# 1-Schematic_TRD_Line_follower_robot.net
KiCad netlist of a schematic drawn in EasyEDA
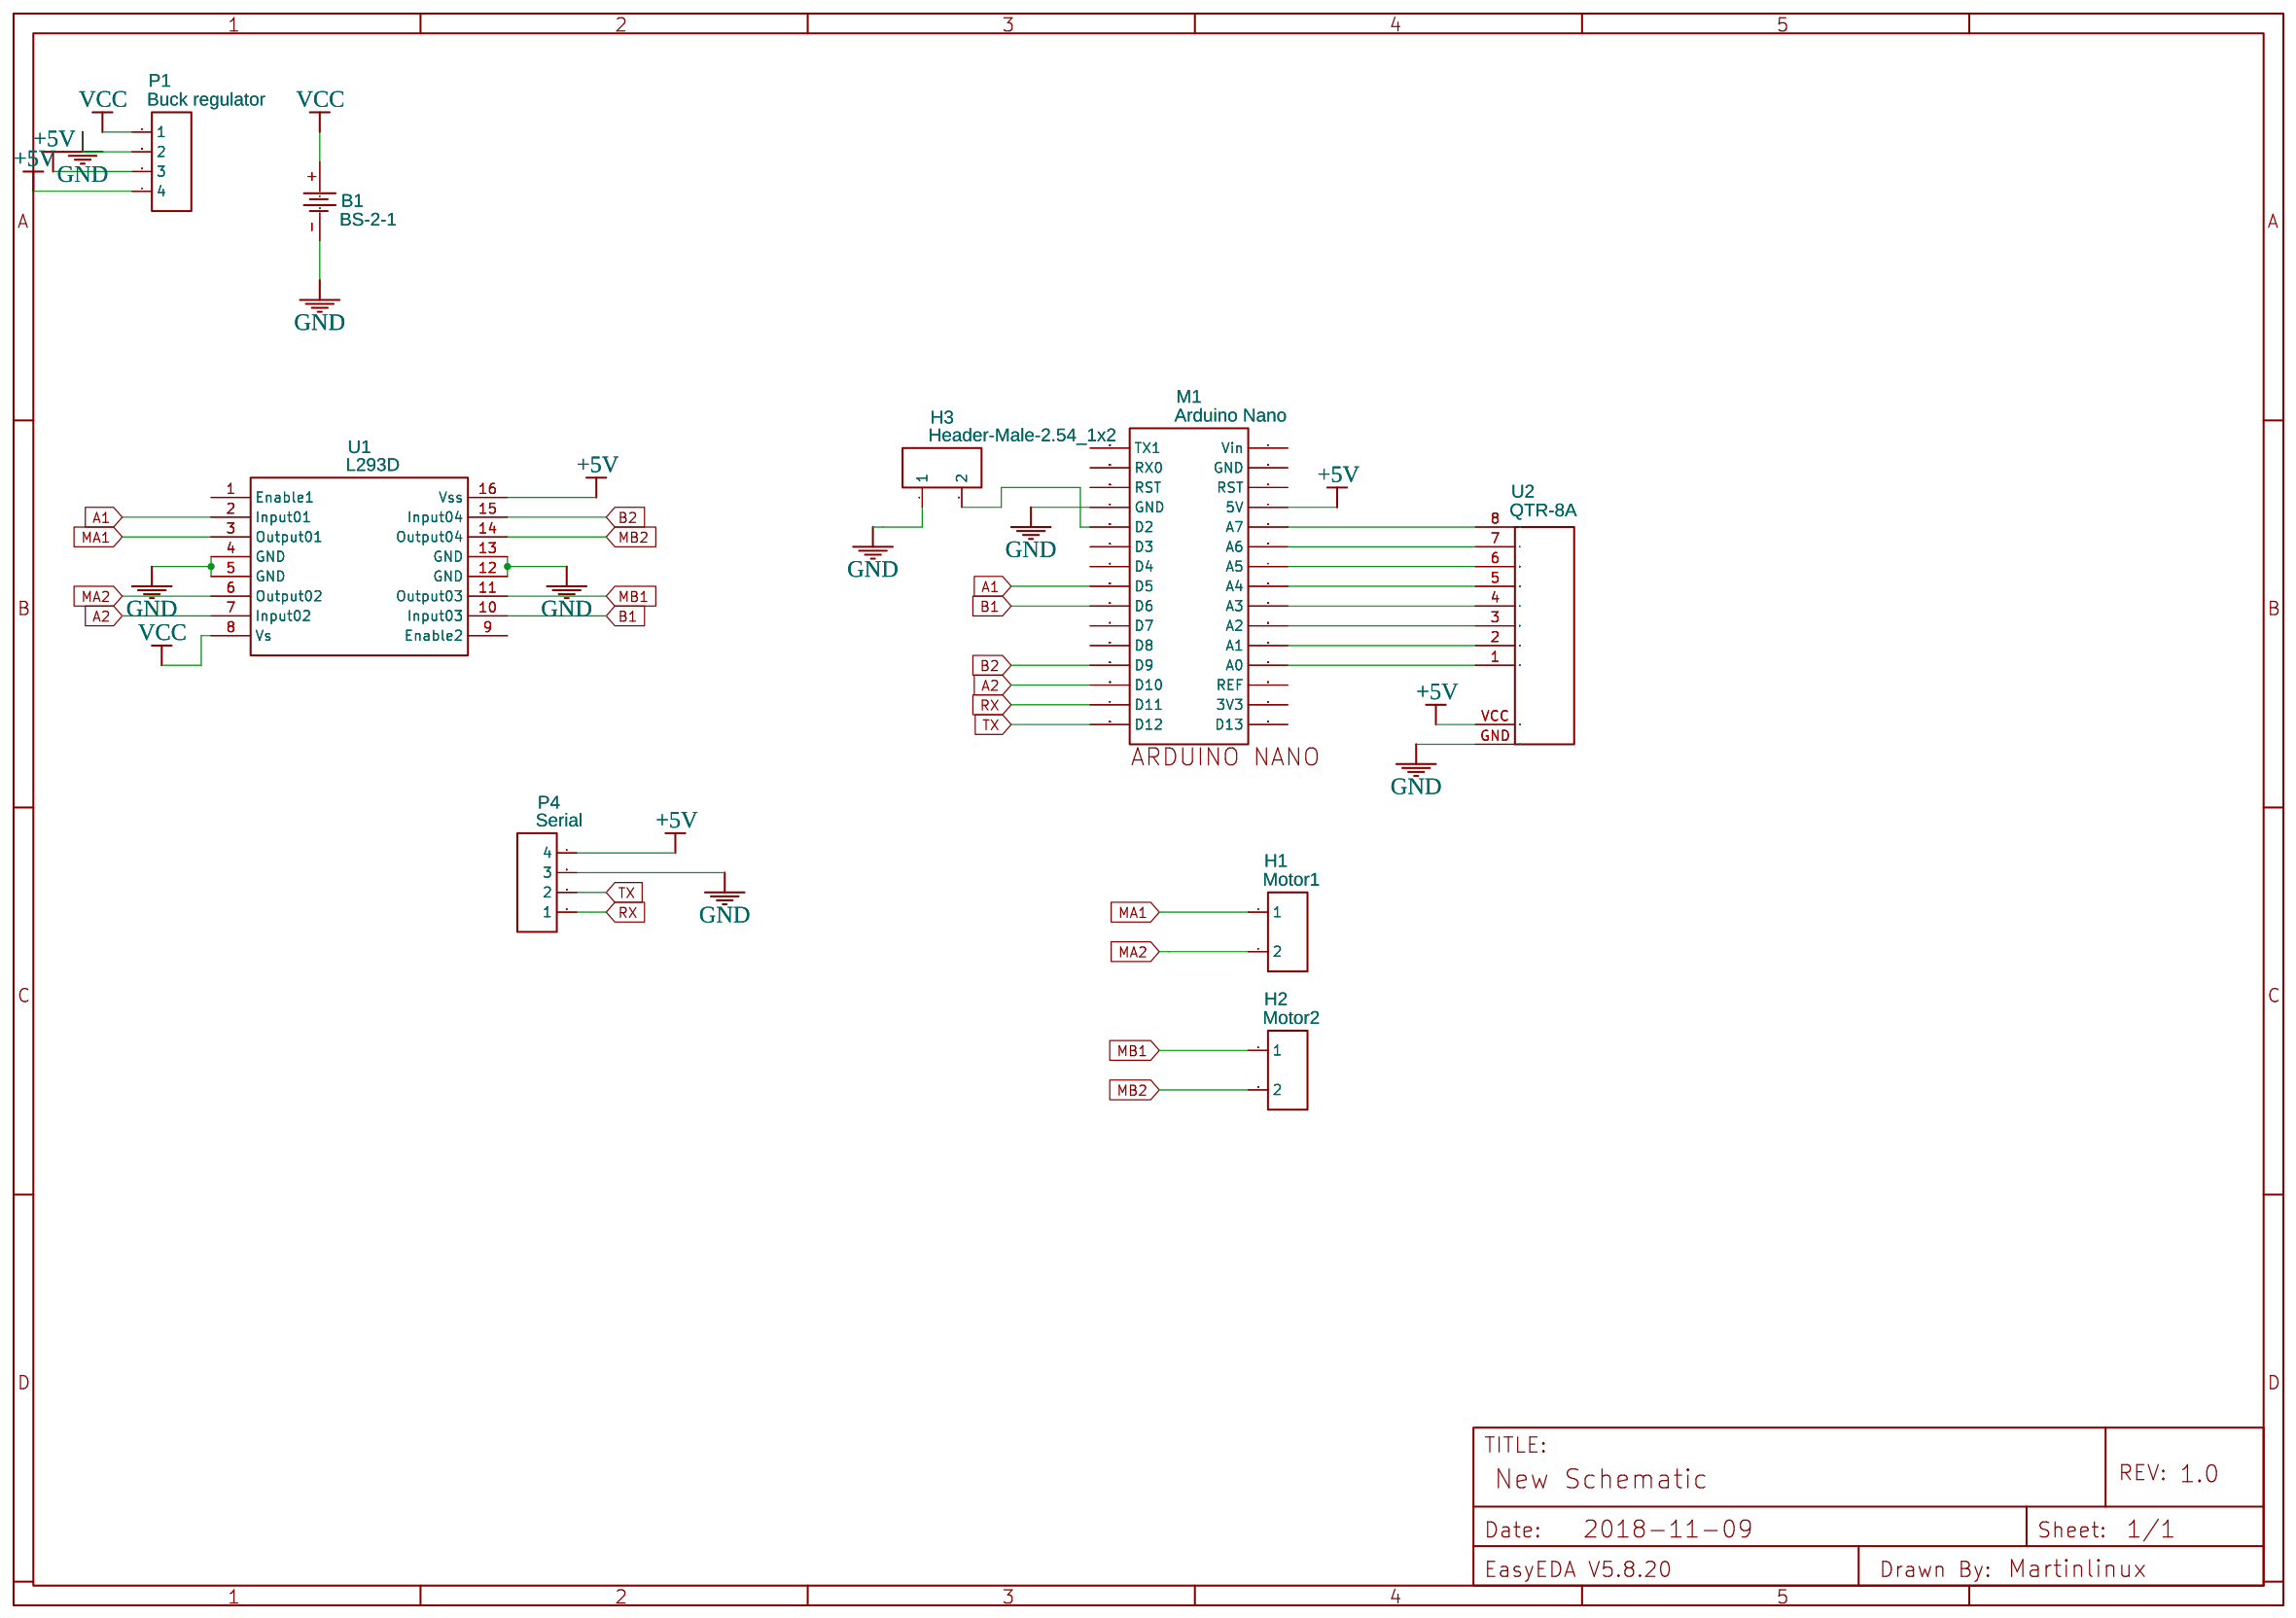
[diagram p0: schematic sheet]

(export (version "E")
  (design (tool "Eeschema 10.0.6"))
  (components
    (comp (ref "B1")
      (value "BS-2-1")
      (fields (field (name "BOM_Supplier Part") "C70376"))
      (libsource (lib "") (part "Unknown_155_95"))
    )
    (comp (ref "H1")
      (value "Motor1")
      (fields (field (name "BOM_Manufacturer Part") "826629-2") (field (name "BOM_Supplier Part") "C86471"))
      (libsource (lib "") (part "Unknown_640_465"))
    )
    (comp (ref "H2")
      (value "Motor2")
      (fields (field (name "BOM_Manufacturer Part") "826629-2") (field (name "BOM_Supplier Part") "C86471"))
      (libsource (lib "") (part "Unknown_640_535"))
    )
    (comp (ref "H3")
      (value "Header-Male-2.54_1x2")
      (fields (field (name "BOM_Manufacturer Part") "826629-2") (field (name "BOM_Supplier Part") "C86471"))
      (libsource (lib "") (part "Unknown_470_235"))
    )
    (comp (ref "M1") (value "Arduino Nano") (libsource (lib "") (part "Unknown_565_210")))
    (comp (ref "P1")
      (value "Buck regulator")
      (fields
        (field (name "BOM_Manufacturer Part") "Header-Female-2.54_1x4")
        (field (name "BOM_Supplier Part") "C124413")
      )
      (libsource (lib "") (part "Unknown_75_75"))
    )
    (comp (ref "P4")
      (value "Serial")
      (fields
        (field (name "BOM_Manufacturer Part") "Header-Female-2.54_1x4")
        (field (name "BOM_Supplier Part") "C124413")
      )
      (libsource (lib "") (part "Unknown_270_440"))
    )
    (comp (ref "U1")
      (value "L293D")
      (fields (field (name "BOM_Supplier Part") "C12340"))
      (libsource (lib "") (part "Unknown_175_280"))
    )
    (comp (ref "U2")
      (value "QTR-8A")
      (fields (field (name "BOM_Manufacturer Part") "?"))
      (libsource (lib "") (part "Unknown_800_360"))
    )
  )
  (nets
    (net (code "1") (name "+5V") (class "Default")
      (node (ref "M1") (pin "4") (pinfunction "5V_4") (pintype "unspecified"))
      (node (ref "P1") (pin "3") (pinfunction "3_3") (pintype "input"))
      (node (ref "P1") (pin "4") (pinfunction "4_4") (pintype "input"))
      (node (ref "P4") (pin "4") (pinfunction "4_4") (pintype "input"))
      (node (ref "U1") (pin "16") (pinfunction "Vss_16") (pintype "unspecified"))
      (node (ref "U2") (pin "VCC") (pinfunction "9_VCC") (pintype "unspecified"))
    )
    (net (code "2") (name "A1") (class "Default")
      (node (ref "M1") (pin "23") (pinfunction "D5_23") (pintype "unspecified"))
      (node (ref "U1") (pin "2") (pinfunction "Input01_2") (pintype "unspecified"))
    )
    (net (code "3") (name "A2") (class "Default")
      (node (ref "M1") (pin "18") (pinfunction "D10_18") (pintype "unspecified"))
      (node (ref "U1") (pin "7") (pinfunction "Input02_7") (pintype "unspecified"))
    )
    (net (code "4") (name "B1") (class "Default")
      (node (ref "M1") (pin "22") (pinfunction "D6_22") (pintype "unspecified"))
      (node (ref "U1") (pin "10") (pinfunction "Input03_10") (pintype "unspecified"))
    )
    (net (code "5") (name "B2") (class "Default")
      (node (ref "M1") (pin "19") (pinfunction "D9_19") (pintype "unspecified"))
      (node (ref "U1") (pin "15") (pinfunction "Input04_15") (pintype "unspecified"))
    )
    (net (code "6") (name "GND") (class "Default")
      (node (ref "B1") (pin "-") (pinfunction "2_-") (pintype "input"))
      (node (ref "H3") (pin "1") (pinfunction "1_1") (pintype "unspecified"))
      (node (ref "M1") (pin "27") (pinfunction "GND_27") (pintype "unspecified"))
      (node (ref "P1") (pin "2") (pinfunction "2_2") (pintype "input"))
      (node (ref "P4") (pin "3") (pinfunction "3_3") (pintype "input"))
      (node (ref "U1") (pin "12") (pinfunction "GND_12") (pintype "unspecified"))
      (node (ref "U1") (pin "13") (pinfunction "GND_13") (pintype "unspecified"))
      (node (ref "U1") (pin "4") (pinfunction "GND_4") (pintype "unspecified"))
      (node (ref "U1") (pin "5") (pinfunction "GND_5") (pintype "unspecified"))
      (node (ref "U2") (pin "GND") (pinfunction "1_GND") (pintype "unspecified"))
    )
    (net (code "7") (name "MA1") (class "Default")
      (node (ref "H1") (pin "1") (pinfunction "1_1") (pintype "unspecified"))
      (node (ref "U1") (pin "3") (pinfunction "Output01_3") (pintype "unspecified"))
    )
    (net (code "8") (name "MA2") (class "Default")
      (node (ref "H1") (pin "2") (pinfunction "2_2") (pintype "unspecified"))
      (node (ref "U1") (pin "6") (pinfunction "Output02_6") (pintype "unspecified"))
    )
    (net (code "9") (name "MB1") (class "Default")
      (node (ref "H2") (pin "1") (pinfunction "1_1") (pintype "unspecified"))
      (node (ref "U1") (pin "11") (pinfunction "Output03_11") (pintype "unspecified"))
    )
    (net (code "10") (name "MB2") (class "Default")
      (node (ref "H2") (pin "2") (pinfunction "2_2") (pintype "unspecified"))
      (node (ref "U1") (pin "14") (pinfunction "Output04_14") (pintype "unspecified"))
    )
    (net (code "11") (name "Net-(M1-A0)") (class "Default")
      (node (ref "M1") (pin "12") (pinfunction "A0_12") (pintype "unspecified"))
      (node (ref "U2") (pin "1") (pinfunction "1_1") (pintype "unspecified"))
    )
    (net (code "12") (name "Net-(M1-A1)") (class "Default")
      (node (ref "M1") (pin "11") (pinfunction "A1_11") (pintype "unspecified"))
      (node (ref "U2") (pin "2") (pinfunction "2_2") (pintype "unspecified"))
    )
    (net (code "13") (name "Net-(M1-A2)") (class "Default")
      (node (ref "M1") (pin "10") (pinfunction "A2_10") (pintype "unspecified"))
      (node (ref "U2") (pin "3") (pinfunction "3_3") (pintype "unspecified"))
    )
    (net (code "14") (name "Net-(M1-A3)") (class "Default")
      (node (ref "M1") (pin "9") (pinfunction "A3_9") (pintype "unspecified"))
      (node (ref "U2") (pin "4") (pinfunction "4_4") (pintype "unspecified"))
    )
    (net (code "15") (name "Net-(M1-A4)") (class "Default")
      (node (ref "M1") (pin "8") (pinfunction "A4_8") (pintype "unspecified"))
      (node (ref "U2") (pin "5") (pinfunction "5_5") (pintype "unspecified"))
    )
    (net (code "16") (name "Net-(M1-A5)") (class "Default")
      (node (ref "M1") (pin "7") (pinfunction "A5_7") (pintype "unspecified"))
      (node (ref "U2") (pin "6") (pinfunction "6_6") (pintype "unspecified"))
    )
    (net (code "17") (name "Net-(M1-A6)") (class "Default")
      (node (ref "M1") (pin "6") (pinfunction "A6_6") (pintype "unspecified"))
      (node (ref "U2") (pin "7") (pinfunction "7_7") (pintype "unspecified"))
    )
    (net (code "18") (name "Net-(M1-A7)") (class "Default")
      (node (ref "M1") (pin "5") (pinfunction "A7_5") (pintype "unspecified"))
      (node (ref "U2") (pin "8") (pinfunction "8_8") (pintype "unspecified"))
    )
    (net (code "19") (name "Net-(M1-D2)") (class "Default")
      (node (ref "H3") (pin "2") (pinfunction "2_2") (pintype "unspecified"))
      (node (ref "M1") (pin "26") (pinfunction "D2_26") (pintype "unspecified"))
    )
    (net (code "20") (name "RX") (class "Default")
      (node (ref "M1") (pin "17") (pinfunction "D11_17") (pintype "unspecified"))
      (node (ref "P4") (pin "1") (pinfunction "1_1") (pintype "input"))
    )
    (net (code "21") (name "TX") (class "Default")
      (node (ref "M1") (pin "16") (pinfunction "D12_16") (pintype "unspecified"))
      (node (ref "P4") (pin "2") (pinfunction "2_2") (pintype "input"))
    )
    (net (code "22") (name "VCC") (class "Default")
      (node (ref "B1") (pin "+") (pinfunction "1_+") (pintype "input"))
      (node (ref "P1") (pin "1") (pinfunction "1_1") (pintype "input"))
      (node (ref "U1") (pin "8") (pinfunction "Vs_8") (pintype "unspecified"))
    )
    (net (code "23") (name "unconnected-(M1-3V3-Pad14)") (class "Default")
      (node (ref "M1") (pin "14") (pinfunction "3V3_14") (pintype "unspecified"))
    )
    (net (code "24") (name "unconnected-(M1-D3-Pad25)") (class "Default")
      (node (ref "M1") (pin "25") (pinfunction "D3_25") (pintype "unspecified"))
    )
    (net (code "25") (name "unconnected-(M1-D4-Pad24)") (class "Default")
      (node (ref "M1") (pin "24") (pinfunction "D4_24") (pintype "unspecified"))
    )
    (net (code "26") (name "unconnected-(M1-D7-Pad21)") (class "Default")
      (node (ref "M1") (pin "21") (pinfunction "D7_21") (pintype "unspecified"))
    )
    (net (code "27") (name "unconnected-(M1-D8-Pad20)") (class "Default")
      (node (ref "M1") (pin "20") (pinfunction "D8_20") (pintype "unspecified"))
    )
    (net (code "28") (name "unconnected-(M1-D13-Pad15)") (class "Default")
      (node (ref "M1") (pin "15") (pinfunction "D13_15") (pintype "unspecified"))
    )
    (net (code "29") (name "unconnected-(M1-GND-Pad2)") (class "Default")
      (node (ref "M1") (pin "2") (pinfunction "GND_2") (pintype "unspecified"))
    )
    (net (code "30") (name "unconnected-(M1-REF-Pad13)") (class "Default")
      (node (ref "M1") (pin "13") (pinfunction "REF_13") (pintype "unspecified"))
    )
    (net (code "31") (name "unconnected-(M1-RST-Pad3)") (class "Default")
      (node (ref "M1") (pin "3") (pinfunction "RST_3") (pintype "unspecified"))
    )
    (net (code "32") (name "unconnected-(M1-RST-Pad28)") (class "Default")
      (node (ref "M1") (pin "28") (pinfunction "RST_28") (pintype "unspecified"))
    )
    (net (code "33") (name "unconnected-(M1-RX0-Pad29)") (class "Default")
      (node (ref "M1") (pin "29") (pinfunction "RX0_29") (pintype "unspecified"))
    )
    (net (code "34") (name "unconnected-(M1-TX1-Pad30)") (class "Default")
      (node (ref "M1") (pin "30") (pinfunction "TX1_30") (pintype "unspecified"))
    )
    (net (code "35") (name "unconnected-(M1-Vin-Pad1)") (class "Default")
      (node (ref "M1") (pin "1") (pinfunction "Vin_1") (pintype "unspecified"))
    )
    (net (code "36") (name "unconnected-(U1-Enable1-Pad1)") (class "Default")
      (node (ref "U1") (pin "1") (pinfunction "Enable1_1") (pintype "unspecified"))
    )
    (net (code "37") (name "unconnected-(U1-Enable2-Pad9)") (class "Default")
      (node (ref "U1") (pin "9") (pinfunction "Enable2_9") (pintype "unspecified"))
    )
  )
)
